# edition_3test.net
KiCad netlist of a schematic drawn in EAGLE
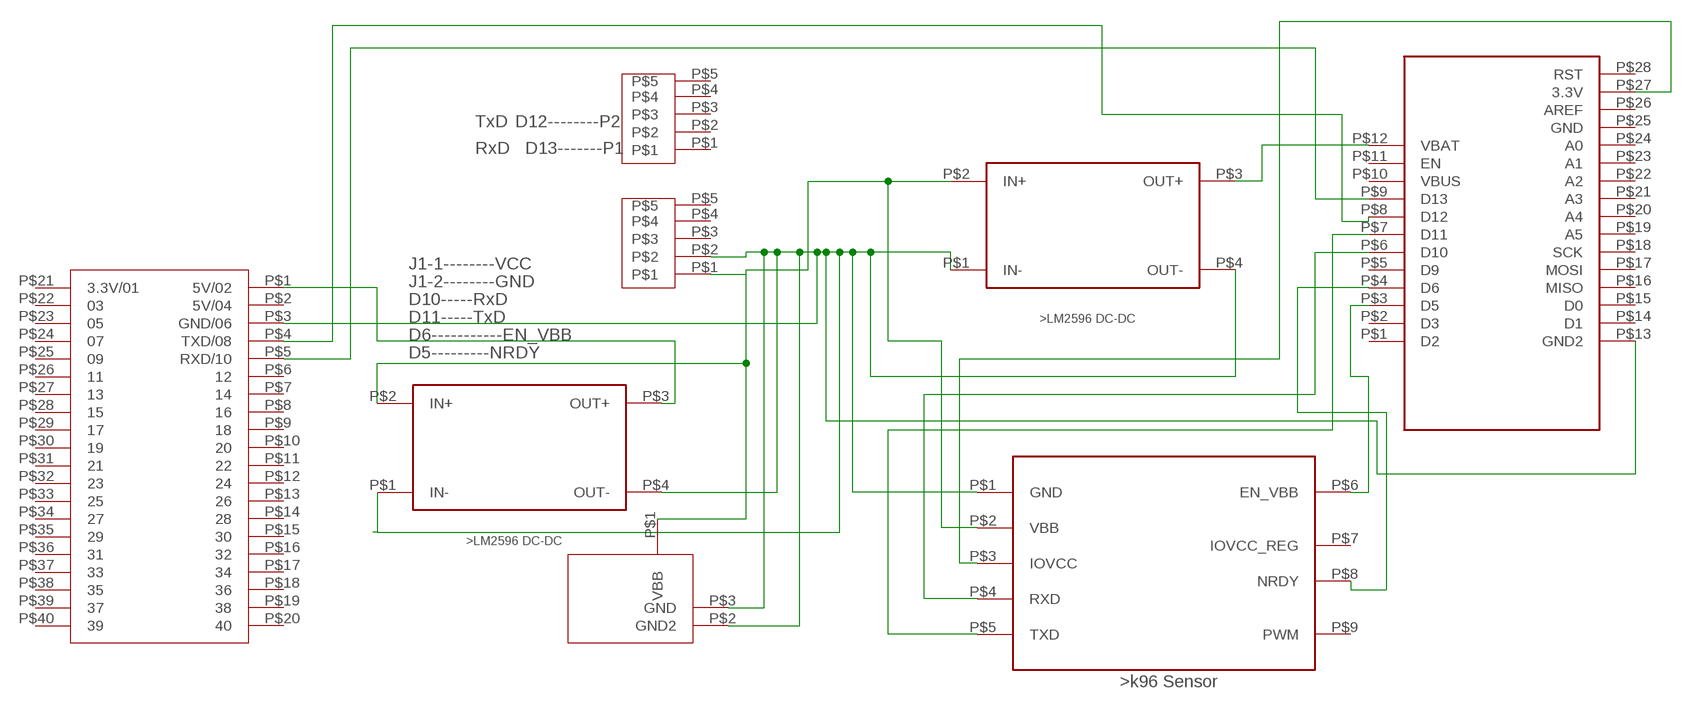
[diagram p0: schematic, sheet 1]

(export (version "E")
  (design (tool "Eeschema 10.0.6"))
  (components
    (comp (ref "DCDC1")
      (value "DCDC")
      (footprint "eagle-import:DCDC")
      (libsource (lib "eagle-import") (part "DCDC"))
    )
    (comp (ref "DCDC2")
      (value "DCDC")
      (footprint "eagle-import:DCDC")
      (libsource (lib "eagle-import") (part "DCDC"))
    )
    (comp (ref "FEATHER1")
      (value "FEATHER")
      (footprint "eagle-import:FEATHER")
      (libsource (lib "eagle-import") (part "FEATHER"))
    )
    (comp (ref "K96SENSOR1")
      (value "K96SENSOR")
      (footprint "eagle-import:K96SENSOR")
      (libsource (lib "eagle-import") (part "K96SENSOR"))
    )
    (comp (ref "PIN1")
      (value "PIN")
      (footprint "eagle-import:PIN")
      (libsource (lib "eagle-import") (part "PIN"))
    )
    (comp (ref "PIN2")
      (value "PIN")
      (footprint "eagle-import:PIN")
      (libsource (lib "eagle-import") (part "PIN"))
    )
    (comp (ref "U$1")
      (value "POWER")
      (footprint "eagle-import:POWERIN")
      (libsource (lib "eagle-import") (part "POWER"))
    )
    (comp (ref "U$2")
      (value "RASPBERRYPI")
      (footprint "eagle-import:RASPBERRYPI")
      (libsource (lib "eagle-import") (part "RASPBERRYPI"))
    )
  )
  (nets
    (net (code "1") (name "Net-(DCDC1-IN+)") (class "Default")
      (node (ref "DCDC1") (pin "P$2") (pinfunction "IN+_P$2") (pintype "bidirectional"))
      (node (ref "DCDC2") (pin "P$2") (pinfunction "IN+_P$2") (pintype "bidirectional"))
      (node (ref "K96SENSOR1") (pin "P$2") (pinfunction "VBB_P$2") (pintype "bidirectional"))
      (node (ref "PIN1") (pin "P$1") (pinfunction "P$1_P$1") (pintype "bidirectional"))
      (node (ref "U$1") (pin "P$1") (pinfunction "VBB_P$1") (pintype "bidirectional"))
    )
    (net (code "2") (name "Net-(DCDC1-IN-)") (class "Default")
      (node (ref "DCDC1") (pin "P$1") (pinfunction "IN-_P$1") (pintype "bidirectional"))
      (node (ref "DCDC1") (pin "P$4") (pinfunction "OUT-_P$4") (pintype "bidirectional"))
      (node (ref "DCDC2") (pin "P$1") (pinfunction "IN-_P$1") (pintype "bidirectional"))
      (node (ref "DCDC2") (pin "P$4") (pinfunction "OUT-_P$4") (pintype "bidirectional"))
      (node (ref "FEATHER1") (pin "P$13") (pinfunction "GND2_P$13") (pintype "bidirectional"))
      (node (ref "K96SENSOR1") (pin "P$1") (pinfunction "GND_P$1") (pintype "bidirectional"))
      (node (ref "PIN1") (pin "P$2") (pinfunction "P$2_P$2") (pintype "bidirectional"))
      (node (ref "U$1") (pin "P$2") (pinfunction "GND2_P$2") (pintype "bidirectional"))
      (node (ref "U$1") (pin "P$3") (pinfunction "GND_P$3") (pintype "bidirectional"))
      (node (ref "U$2") (pin "P$3") (pinfunction "GND/06_P$3") (pintype "bidirectional"))
    )
    (net (code "3") (name "Net-(DCDC1-OUT+)") (class "Default")
      (node (ref "DCDC1") (pin "P$3") (pinfunction "OUT+_P$3") (pintype "bidirectional"))
      (node (ref "FEATHER1") (pin "P$12") (pinfunction "VBAT_P$12") (pintype "bidirectional"))
    )
    (net (code "4") (name "Net-(DCDC2-OUT+)") (class "Default")
      (node (ref "DCDC2") (pin "P$3") (pinfunction "OUT+_P$3") (pintype "bidirectional"))
      (node (ref "U$2") (pin "P$1") (pinfunction "5V/02_P$1") (pintype "bidirectional"))
    )
    (net (code "5") (name "Net-(FEATHER1-3.3V)") (class "Default")
      (node (ref "FEATHER1") (pin "P$27") (pinfunction "3.3V_P$27") (pintype "bidirectional"))
      (node (ref "K96SENSOR1") (pin "P$3") (pinfunction "IOVCC_P$3") (pintype "bidirectional"))
    )
    (net (code "6") (name "Net-(FEATHER1-D5)") (class "Default")
      (node (ref "FEATHER1") (pin "P$3") (pinfunction "D5_P$3") (pintype "bidirectional"))
      (node (ref "K96SENSOR1") (pin "P$6") (pinfunction "EN_VBB_P$6") (pintype "bidirectional"))
    )
    (net (code "7") (name "Net-(FEATHER1-D6)") (class "Default")
      (node (ref "FEATHER1") (pin "P$4") (pinfunction "D6_P$4") (pintype "bidirectional"))
      (node (ref "K96SENSOR1") (pin "P$8") (pinfunction "NRDY_P$8") (pintype "bidirectional"))
    )
    (net (code "8") (name "Net-(FEATHER1-D10)") (class "Default")
      (node (ref "FEATHER1") (pin "P$6") (pinfunction "D10_P$6") (pintype "bidirectional"))
      (node (ref "K96SENSOR1") (pin "P$4") (pinfunction "RXD_P$4") (pintype "bidirectional"))
    )
    (net (code "9") (name "Net-(FEATHER1-D11)") (class "Default")
      (node (ref "FEATHER1") (pin "P$7") (pinfunction "D11_P$7") (pintype "bidirectional"))
      (node (ref "K96SENSOR1") (pin "P$5") (pinfunction "TXD_P$5") (pintype "bidirectional"))
    )
    (net (code "10") (name "Net-(FEATHER1-D12)") (class "Default")
      (node (ref "FEATHER1") (pin "P$8") (pinfunction "D12_P$8") (pintype "bidirectional"))
      (node (ref "U$2") (pin "P$4") (pinfunction "TXD/08_P$4") (pintype "bidirectional"))
    )
    (net (code "11") (name "Net-(FEATHER1-D13)") (class "Default")
      (node (ref "FEATHER1") (pin "P$9") (pinfunction "D13_P$9") (pintype "bidirectional"))
      (node (ref "U$2") (pin "P$5") (pinfunction "RXD/10_P$5") (pintype "bidirectional"))
    )
    (net (code "12") (name "unconnected-(FEATHER1-A0-PadP$24)") (class "Default")
      (node (ref "FEATHER1") (pin "P$24") (pinfunction "A0_P$24") (pintype "bidirectional"))
    )
    (net (code "13") (name "unconnected-(FEATHER1-A1-PadP$23)") (class "Default")
      (node (ref "FEATHER1") (pin "P$23") (pinfunction "A1_P$23") (pintype "bidirectional"))
    )
    (net (code "14") (name "unconnected-(FEATHER1-A2-PadP$22)") (class "Default")
      (node (ref "FEATHER1") (pin "P$22") (pinfunction "A2_P$22") (pintype "bidirectional"))
    )
    (net (code "15") (name "unconnected-(FEATHER1-A3-PadP$21)") (class "Default")
      (node (ref "FEATHER1") (pin "P$21") (pinfunction "A3_P$21") (pintype "bidirectional"))
    )
    (net (code "16") (name "unconnected-(FEATHER1-A4-PadP$20)") (class "Default")
      (node (ref "FEATHER1") (pin "P$20") (pinfunction "A4_P$20") (pintype "bidirectional"))
    )
    (net (code "17") (name "unconnected-(FEATHER1-A5-PadP$19)") (class "Default")
      (node (ref "FEATHER1") (pin "P$19") (pinfunction "A5_P$19") (pintype "bidirectional"))
    )
    (net (code "18") (name "unconnected-(FEATHER1-AREF-PadP$26)") (class "Default")
      (node (ref "FEATHER1") (pin "P$26") (pinfunction "AREF_P$26") (pintype "bidirectional"))
    )
    (net (code "19") (name "unconnected-(FEATHER1-D0-PadP$15)") (class "Default")
      (node (ref "FEATHER1") (pin "P$15") (pinfunction "D0_P$15") (pintype "bidirectional"))
    )
    (net (code "20") (name "unconnected-(FEATHER1-D1-PadP$14)") (class "Default")
      (node (ref "FEATHER1") (pin "P$14") (pinfunction "D1_P$14") (pintype "bidirectional"))
    )
    (net (code "21") (name "unconnected-(FEATHER1-D2-PadP$1)") (class "Default")
      (node (ref "FEATHER1") (pin "P$1") (pinfunction "D2_P$1") (pintype "bidirectional"))
    )
    (net (code "22") (name "unconnected-(FEATHER1-D3-PadP$2)") (class "Default")
      (node (ref "FEATHER1") (pin "P$2") (pinfunction "D3_P$2") (pintype "bidirectional"))
    )
    (net (code "23") (name "unconnected-(FEATHER1-D9-PadP$5)") (class "Default")
      (node (ref "FEATHER1") (pin "P$5") (pinfunction "D9_P$5") (pintype "bidirectional"))
    )
    (net (code "24") (name "unconnected-(FEATHER1-EN-PadP$11)") (class "Default")
      (node (ref "FEATHER1") (pin "P$11") (pinfunction "EN_P$11") (pintype "bidirectional"))
    )
    (net (code "25") (name "unconnected-(FEATHER1-GND-PadP$25)") (class "Default")
      (node (ref "FEATHER1") (pin "P$25") (pinfunction "GND_P$25") (pintype "bidirectional"))
    )
    (net (code "26") (name "unconnected-(FEATHER1-MISO-PadP$16)") (class "Default")
      (node (ref "FEATHER1") (pin "P$16") (pinfunction "MISO_P$16") (pintype "bidirectional"))
    )
    (net (code "27") (name "unconnected-(FEATHER1-MOSI-PadP$17)") (class "Default")
      (node (ref "FEATHER1") (pin "P$17") (pinfunction "MOSI_P$17") (pintype "bidirectional"))
    )
    (net (code "28") (name "unconnected-(FEATHER1-RST-PadP$28)") (class "Default")
      (node (ref "FEATHER1") (pin "P$28") (pinfunction "RST_P$28") (pintype "bidirectional"))
    )
    (net (code "29") (name "unconnected-(FEATHER1-SCK-PadP$18)") (class "Default")
      (node (ref "FEATHER1") (pin "P$18") (pinfunction "SCK_P$18") (pintype "bidirectional"))
    )
    (net (code "30") (name "unconnected-(FEATHER1-VBUS-PadP$10)") (class "Default")
      (node (ref "FEATHER1") (pin "P$10") (pinfunction "VBUS_P$10") (pintype "bidirectional"))
    )
    (net (code "31") (name "unconnected-(K96SENSOR1-IOVCC_REG-PadP$7)") (class "Default")
      (node (ref "K96SENSOR1") (pin "P$7") (pinfunction "IOVCC_REG_P$7") (pintype "bidirectional"))
    )
    (net (code "32") (name "unconnected-(K96SENSOR1-PWM-PadP$9)") (class "Default")
      (node (ref "K96SENSOR1") (pin "P$9") (pinfunction "PWM_P$9") (pintype "bidirectional"))
    )
    (net (code "33") (name "unconnected-(PIN1-PadP$3)") (class "Default")
      (node (ref "PIN1") (pin "P$3") (pinfunction "P$3_P$3") (pintype "bidirectional"))
    )
    (net (code "34") (name "unconnected-(PIN1-PadP$4)") (class "Default")
      (node (ref "PIN1") (pin "P$4") (pinfunction "P$4_P$4") (pintype "bidirectional"))
    )
    (net (code "35") (name "unconnected-(PIN1-PadP$5)") (class "Default")
      (node (ref "PIN1") (pin "P$5") (pinfunction "P$5_P$5") (pintype "bidirectional"))
    )
    (net (code "36") (name "unconnected-(PIN2-PadP$1)") (class "Default")
      (node (ref "PIN2") (pin "P$1") (pinfunction "P$1_P$1") (pintype "bidirectional"))
    )
    (net (code "37") (name "unconnected-(PIN2-PadP$2)") (class "Default")
      (node (ref "PIN2") (pin "P$2") (pinfunction "P$2_P$2") (pintype "bidirectional"))
    )
    (net (code "38") (name "unconnected-(PIN2-PadP$3)") (class "Default")
      (node (ref "PIN2") (pin "P$3") (pinfunction "P$3_P$3") (pintype "bidirectional"))
    )
    (net (code "39") (name "unconnected-(PIN2-PadP$4)") (class "Default")
      (node (ref "PIN2") (pin "P$4") (pinfunction "P$4_P$4") (pintype "bidirectional"))
    )
    (net (code "40") (name "unconnected-(PIN2-PadP$5)") (class "Default")
      (node (ref "PIN2") (pin "P$5") (pinfunction "P$5_P$5") (pintype "bidirectional"))
    )
    (net (code "41") (name "unconnected-(U$2-03-PadP$22)") (class "Default")
      (node (ref "U$2") (pin "P$22") (pinfunction "03_P$22") (pintype "bidirectional"))
    )
    (net (code "42") (name "unconnected-(U$2-3.3V{slash}01-PadP$21)") (class "Default")
      (node (ref "U$2") (pin "P$21") (pinfunction "3.3V/01_P$21") (pintype "bidirectional"))
    )
    (net (code "43") (name "unconnected-(U$2-05-PadP$23)") (class "Default")
      (node (ref "U$2") (pin "P$23") (pinfunction "05_P$23") (pintype "bidirectional"))
    )
    (net (code "44") (name "unconnected-(U$2-5V{slash}04-PadP$2)") (class "Default")
      (node (ref "U$2") (pin "P$2") (pinfunction "5V/04_P$2") (pintype "bidirectional"))
    )
    (net (code "45") (name "unconnected-(U$2-07-PadP$24)") (class "Default")
      (node (ref "U$2") (pin "P$24") (pinfunction "07_P$24") (pintype "bidirectional"))
    )
    (net (code "46") (name "unconnected-(U$2-09-PadP$25)") (class "Default")
      (node (ref "U$2") (pin "P$25") (pinfunction "09_P$25") (pintype "bidirectional"))
    )
    (net (code "47") (name "unconnected-(U$2-11-PadP$26)") (class "Default")
      (node (ref "U$2") (pin "P$26") (pinfunction "11_P$26") (pintype "bidirectional"))
    )
    (net (code "48") (name "unconnected-(U$2-12-PadP$6)") (class "Default")
      (node (ref "U$2") (pin "P$6") (pinfunction "12_P$6") (pintype "bidirectional"))
    )
    (net (code "49") (name "unconnected-(U$2-13-PadP$27)") (class "Default")
      (node (ref "U$2") (pin "P$27") (pinfunction "13_P$27") (pintype "bidirectional"))
    )
    (net (code "50") (name "unconnected-(U$2-14-PadP$7)") (class "Default")
      (node (ref "U$2") (pin "P$7") (pinfunction "14_P$7") (pintype "bidirectional"))
    )
    (net (code "51") (name "unconnected-(U$2-15-PadP$28)") (class "Default")
      (node (ref "U$2") (pin "P$28") (pinfunction "15_P$28") (pintype "bidirectional"))
    )
    (net (code "52") (name "unconnected-(U$2-16-PadP$8)") (class "Default")
      (node (ref "U$2") (pin "P$8") (pinfunction "16_P$8") (pintype "bidirectional"))
    )
    (net (code "53") (name "unconnected-(U$2-17-PadP$29)") (class "Default")
      (node (ref "U$2") (pin "P$29") (pinfunction "17_P$29") (pintype "bidirectional"))
    )
    (net (code "54") (name "unconnected-(U$2-18-PadP$9)") (class "Default")
      (node (ref "U$2") (pin "P$9") (pinfunction "18_P$9") (pintype "bidirectional"))
    )
    (net (code "55") (name "unconnected-(U$2-19-PadP$30)") (class "Default")
      (node (ref "U$2") (pin "P$30") (pinfunction "19_P$30") (pintype "bidirectional"))
    )
    (net (code "56") (name "unconnected-(U$2-20-PadP$10)") (class "Default")
      (node (ref "U$2") (pin "P$10") (pinfunction "20_P$10") (pintype "bidirectional"))
    )
    (net (code "57") (name "unconnected-(U$2-21-PadP$31)") (class "Default")
      (node (ref "U$2") (pin "P$31") (pinfunction "21_P$31") (pintype "bidirectional"))
    )
    (net (code "58") (name "unconnected-(U$2-22-PadP$11)") (class "Default")
      (node (ref "U$2") (pin "P$11") (pinfunction "22_P$11") (pintype "bidirectional"))
    )
    (net (code "59") (name "unconnected-(U$2-23-PadP$32)") (class "Default")
      (node (ref "U$2") (pin "P$32") (pinfunction "23_P$32") (pintype "bidirectional"))
    )
    (net (code "60") (name "unconnected-(U$2-24-PadP$12)") (class "Default")
      (node (ref "U$2") (pin "P$12") (pinfunction "24_P$12") (pintype "bidirectional"))
    )
    (net (code "61") (name "unconnected-(U$2-25-PadP$33)") (class "Default")
      (node (ref "U$2") (pin "P$33") (pinfunction "25_P$33") (pintype "bidirectional"))
    )
    (net (code "62") (name "unconnected-(U$2-26-PadP$13)") (class "Default")
      (node (ref "U$2") (pin "P$13") (pinfunction "26_P$13") (pintype "bidirectional"))
    )
    (net (code "63") (name "unconnected-(U$2-27-PadP$34)") (class "Default")
      (node (ref "U$2") (pin "P$34") (pinfunction "27_P$34") (pintype "bidirectional"))
    )
    (net (code "64") (name "unconnected-(U$2-28-PadP$14)") (class "Default")
      (node (ref "U$2") (pin "P$14") (pinfunction "28_P$14") (pintype "bidirectional"))
    )
    (net (code "65") (name "unconnected-(U$2-29-PadP$35)") (class "Default")
      (node (ref "U$2") (pin "P$35") (pinfunction "29_P$35") (pintype "bidirectional"))
    )
    (net (code "66") (name "unconnected-(U$2-30-PadP$15)") (class "Default")
      (node (ref "U$2") (pin "P$15") (pinfunction "30_P$15") (pintype "bidirectional"))
    )
    (net (code "67") (name "unconnected-(U$2-31-PadP$36)") (class "Default")
      (node (ref "U$2") (pin "P$36") (pinfunction "31_P$36") (pintype "bidirectional"))
    )
    (net (code "68") (name "unconnected-(U$2-32-PadP$16)") (class "Default")
      (node (ref "U$2") (pin "P$16") (pinfunction "32_P$16") (pintype "bidirectional"))
    )
    (net (code "69") (name "unconnected-(U$2-33-PadP$37)") (class "Default")
      (node (ref "U$2") (pin "P$37") (pinfunction "33_P$37") (pintype "bidirectional"))
    )
    (net (code "70") (name "unconnected-(U$2-34-PadP$17)") (class "Default")
      (node (ref "U$2") (pin "P$17") (pinfunction "34_P$17") (pintype "bidirectional"))
    )
    (net (code "71") (name "unconnected-(U$2-35-PadP$38)") (class "Default")
      (node (ref "U$2") (pin "P$38") (pinfunction "35_P$38") (pintype "bidirectional"))
    )
    (net (code "72") (name "unconnected-(U$2-36-PadP$18)") (class "Default")
      (node (ref "U$2") (pin "P$18") (pinfunction "36_P$18") (pintype "bidirectional"))
    )
    (net (code "73") (name "unconnected-(U$2-37-PadP$39)") (class "Default")
      (node (ref "U$2") (pin "P$39") (pinfunction "37_P$39") (pintype "bidirectional"))
    )
    (net (code "74") (name "unconnected-(U$2-38-PadP$19)") (class "Default")
      (node (ref "U$2") (pin "P$19") (pinfunction "38_P$19") (pintype "bidirectional"))
    )
    (net (code "75") (name "unconnected-(U$2-39-PadP$40)") (class "Default")
      (node (ref "U$2") (pin "P$40") (pinfunction "39_P$40") (pintype "bidirectional"))
    )
    (net (code "76") (name "unconnected-(U$2-40-PadP$20)") (class "Default")
      (node (ref "U$2") (pin "P$20") (pinfunction "40_P$20") (pintype "bidirectional"))
    )
  )
)
